# ST-Link_V3E.net
KiCad netlist of a schematic drawn in Altium Designer
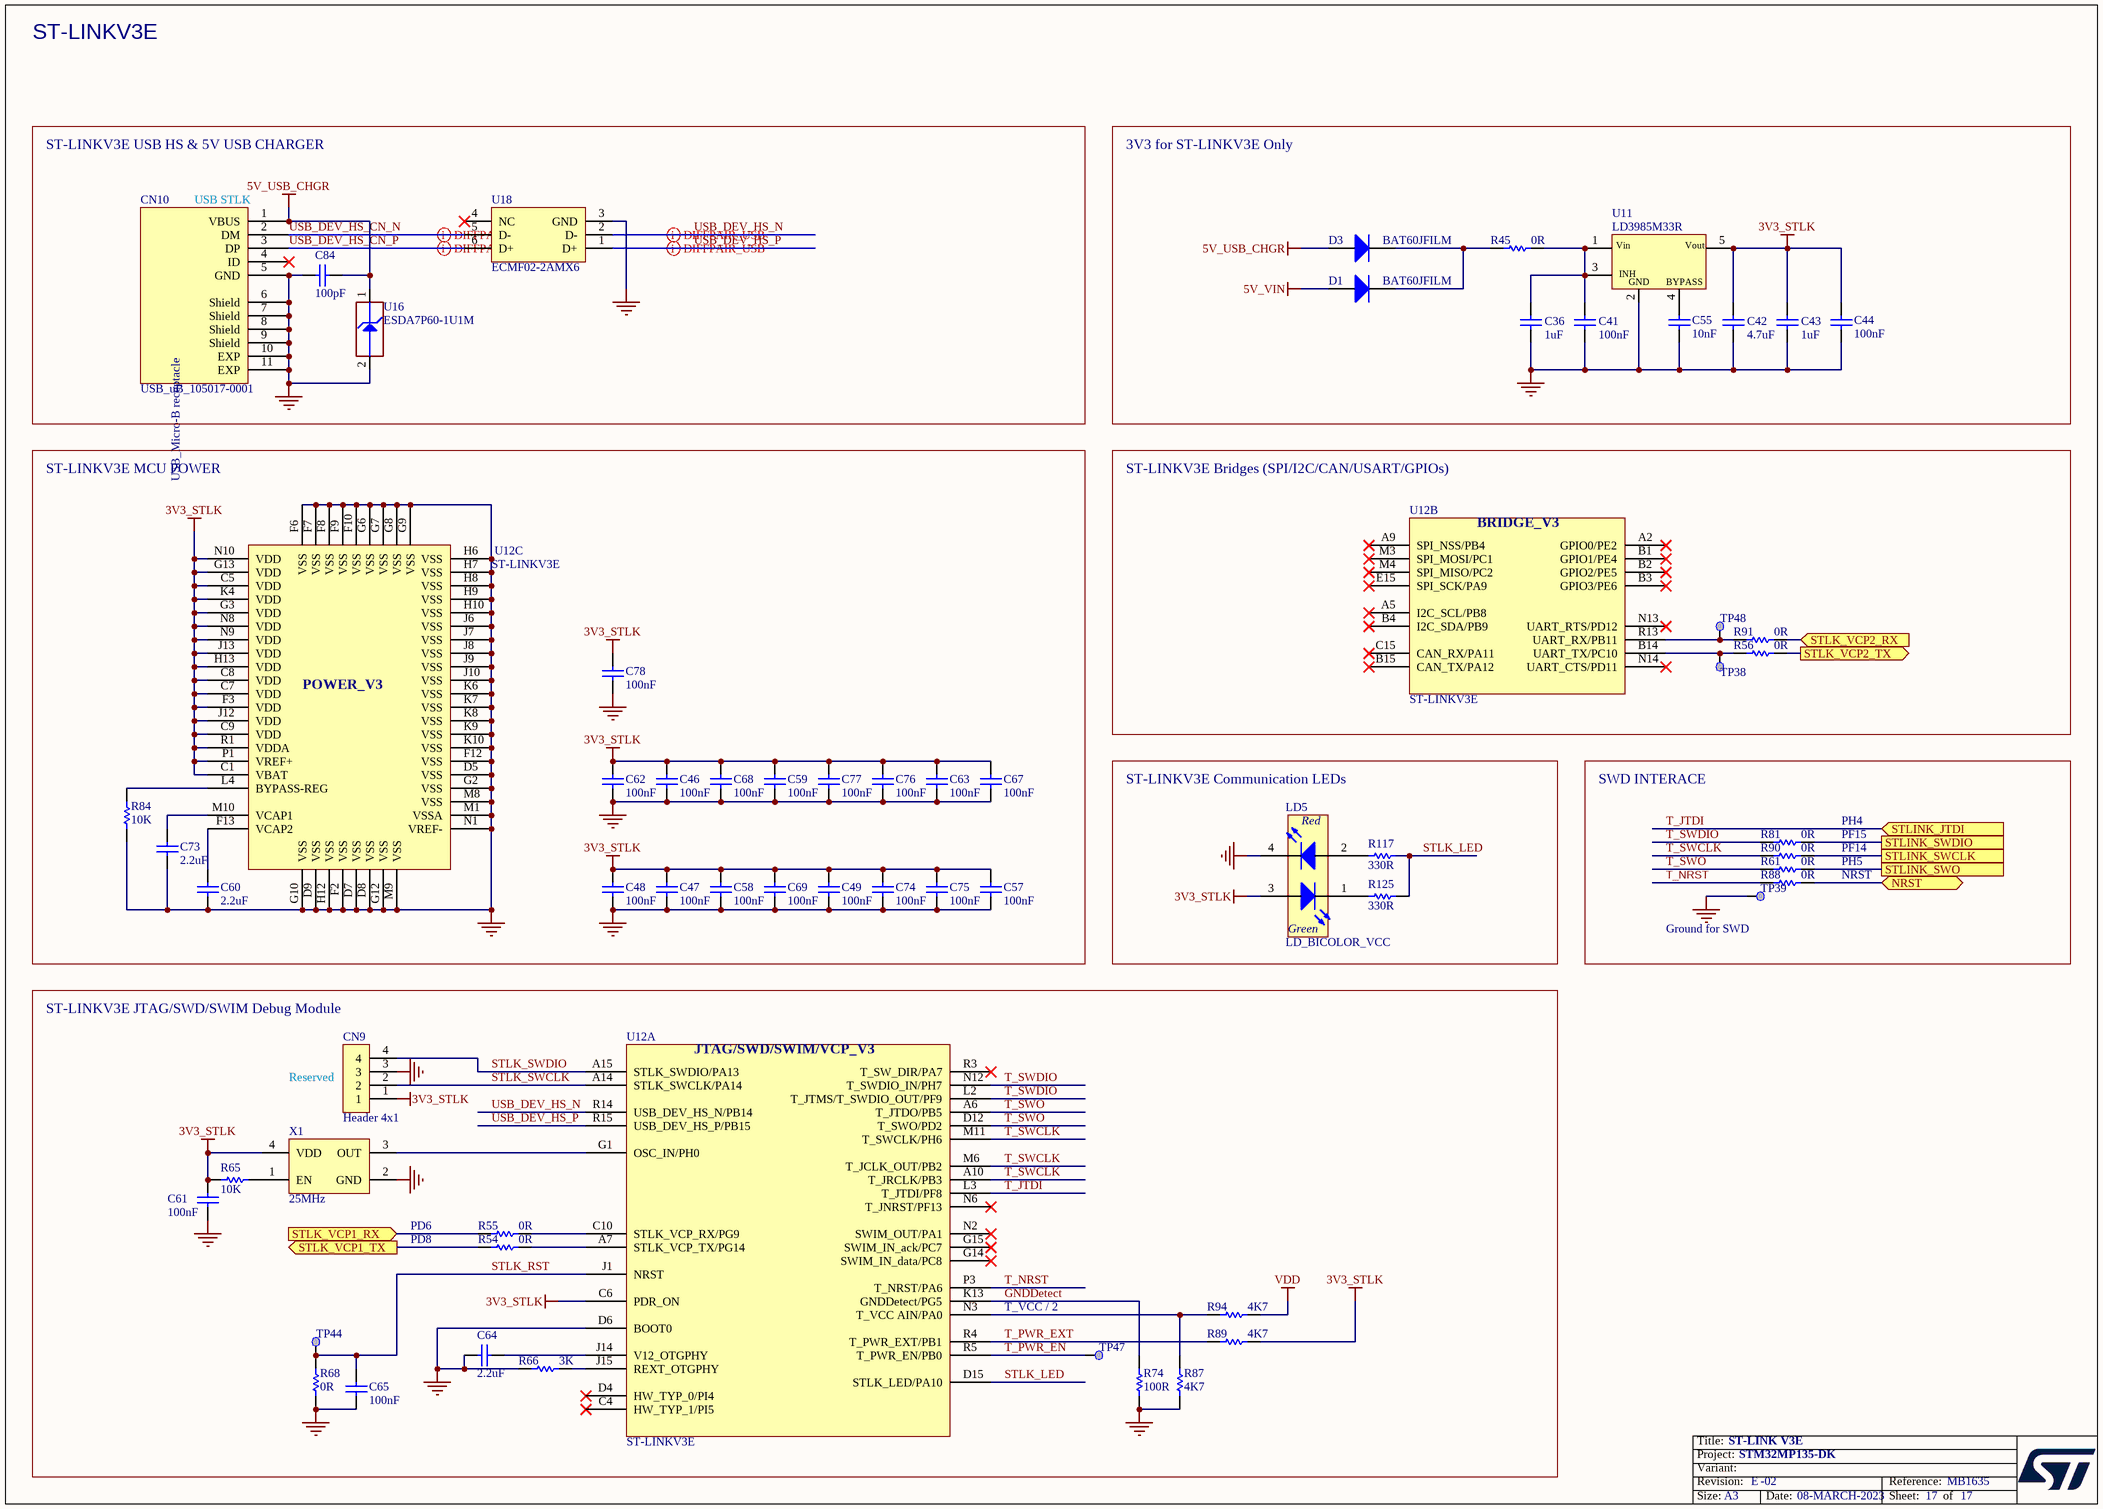
[diagram p0: ST-Link_V3E.SchDoc]

(export (version "E")
  (design (tool "Eeschema 10.0.6"))
  (components
    (comp (ref "C36")
      (value "1uF")
      (footprint "C0402")
      (description "Capacitor, MLCC, 1uF, 25V, X5R, +/-10%, 0402, T=0.5mm")
      (fields
        (field (name "INTERNAL_PART_NUMBER") "MCD-00095")
        (field (name "MANUFACTURER_PART_NUMBER") "GRM155R61E105KA12")
      )
      (libsource (lib "MCD_PARTS_database") (part "Capacitor"))
    )
    (comp (ref "C41")
      (value "100nF")
      (footprint "C0402")
      (description "Capacitor, MLCC, 100nF, 16V, X7R, +/-10%, 0402, T=0.5mm")
      (fields
        (field (name "INTERNAL_PART_NUMBER") "MCD-00006")
        (field (name "MANUFACTURER_PART_NUMBER") "CC0402KRX7R7BB104")
      )
      (libsource (lib "MCD_PARTS_database") (part "Capacitor"))
    )
    (comp (ref "C42")
      (value "4.7uF")
      (footprint "C0402")
      (description "Capacitor, MLCC, 4.7uF, 6V3, X5R, +/-20%, 0402, T=0.5mm")
      (fields
        (field (name "INTERNAL_PART_NUMBER") "MCD-01356")
        (field (name "MANUFACTURER_PART_NUMBER") "GRM155R60J475ME47")
      )
      (libsource (lib "MCD_PARTS_database") (part "Capacitor"))
    )
    (comp (ref "C43")
      (value "1uF")
      (footprint "C0402")
      (description "Capacitor, MLCC, 1uF, 25V, X5R, +/-10%, 0402, T=0.5mm")
      (fields
        (field (name "INTERNAL_PART_NUMBER") "MCD-00095")
        (field (name "MANUFACTURER_PART_NUMBER") "GRM155R61E105KA12")
      )
      (libsource (lib "MCD_PARTS_database") (part "Capacitor"))
    )
    (comp (ref "C44")
      (value "100nF")
      (footprint "C0402")
      (description "Capacitor, MLCC, 100nF, 16V, X7R, +/-10%, 0402, T=0.5mm")
      (fields
        (field (name "INTERNAL_PART_NUMBER") "MCD-00006")
        (field (name "MANUFACTURER_PART_NUMBER") "CC0402KRX7R7BB104")
      )
      (libsource (lib "MCD_PARTS_database") (part "Capacitor"))
    )
    (comp (ref "C46")
      (value "100nF")
      (footprint "C0402")
      (description "Capacitor, MLCC, 100nF, 16V, X7R, +/-10%, 0402, T=0.5mm")
      (fields
        (field (name "INTERNAL_PART_NUMBER") "MCD-00006")
        (field (name "MANUFACTURER_PART_NUMBER") "CC0402KRX7R7BB104")
      )
      (libsource (lib "MCD_PARTS_database") (part "Capacitor"))
    )
    (comp (ref "C47")
      (value "100nF")
      (footprint "C0402")
      (description "Capacitor, MLCC, 100nF, 16V, X7R, +/-10%, 0402, T=0.5mm")
      (fields
        (field (name "INTERNAL_PART_NUMBER") "MCD-00006")
        (field (name "MANUFACTURER_PART_NUMBER") "CC0402KRX7R7BB104")
      )
      (libsource (lib "MCD_PARTS_database") (part "Capacitor"))
    )
    (comp (ref "C48")
      (value "100nF")
      (footprint "C0402")
      (description "Capacitor, MLCC, 100nF, 16V, X7R, +/-10%, 0402, T=0.5mm")
      (fields
        (field (name "INTERNAL_PART_NUMBER") "MCD-00006")
        (field (name "MANUFACTURER_PART_NUMBER") "CC0402KRX7R7BB104")
      )
      (libsource (lib "MCD_PARTS_database") (part "Capacitor"))
    )
    (comp (ref "C49")
      (value "100nF")
      (footprint "C0402")
      (description "Capacitor, MLCC, 100nF, 16V, X7R, +/-10%, 0402, T=0.5mm")
      (fields
        (field (name "INTERNAL_PART_NUMBER") "MCD-00006")
        (field (name "MANUFACTURER_PART_NUMBER") "CC0402KRX7R7BB104")
      )
      (libsource (lib "MCD_PARTS_database") (part "Capacitor"))
    )
    (comp (ref "C55")
      (value "10nF")
      (footprint "C0402")
      (description "Capacitor, MLCC, 10nF, 50V, X7R, +/-10%, 0402, T=0.5mm")
      (fields
        (field (name "INTERNAL_PART_NUMBER") "MCD-02198")
        (field (name "MANUFACTURER_PART_NUMBER") "CC0402KRX7R9BB103")
      )
      (libsource (lib "MCD_PARTS_database") (part "Capacitor"))
    )
    (comp (ref "C57")
      (value "100nF")
      (footprint "C0402")
      (description "Capacitor, MLCC, 100nF, 16V, X7R, +/-10%, 0402, T=0.5mm")
      (fields
        (field (name "INTERNAL_PART_NUMBER") "MCD-00006")
        (field (name "MANUFACTURER_PART_NUMBER") "CC0402KRX7R7BB104")
      )
      (libsource (lib "MCD_PARTS_database") (part "Capacitor"))
    )
    (comp (ref "C58")
      (value "100nF")
      (footprint "C0402")
      (description "Capacitor, MLCC, 100nF, 16V, X7R, +/-10%, 0402, T=0.5mm")
      (fields
        (field (name "INTERNAL_PART_NUMBER") "MCD-00006")
        (field (name "MANUFACTURER_PART_NUMBER") "CC0402KRX7R7BB104")
      )
      (libsource (lib "MCD_PARTS_database") (part "Capacitor"))
    )
    (comp (ref "C59")
      (value "100nF")
      (footprint "C0402")
      (description "Capacitor, MLCC, 100nF, 16V, X7R, +/-10%, 0402, T=0.5mm")
      (fields
        (field (name "INTERNAL_PART_NUMBER") "MCD-00006")
        (field (name "MANUFACTURER_PART_NUMBER") "CC0402KRX7R7BB104")
      )
      (libsource (lib "MCD_PARTS_database") (part "Capacitor"))
    )
    (comp (ref "C60")
      (value "2.2uF")
      (footprint "C0201_H0P5")
      (description "Capacitor, MLCC, 2.2uF, 10V, X5R,+/-10%, 0201, T=0.5mm")
      (fields
        (field (name "INTERNAL_PART_NUMBER") "MCD-02235")
        (field (name "MANUFACTURER_PART_NUMBER") "GRM033R61A225KE47D")
      )
      (libsource (lib "MCD_PARTS_database") (part "Capacitor"))
    )
    (comp (ref "C61")
      (value "100nF")
      (footprint "C0402")
      (description "Capacitor, MLCC, 100nF, 16V, X7R, +/-10%, 0402, T=0.5mm")
      (fields
        (field (name "INTERNAL_PART_NUMBER") "MCD-00006")
        (field (name "MANUFACTURER_PART_NUMBER") "CC0402KRX7R7BB104")
      )
      (libsource (lib "MCD_PARTS_database") (part "Capacitor"))
    )
    (comp (ref "C62")
      (value "100nF")
      (footprint "C0402")
      (description "Capacitor, MLCC, 100nF, 16V, X7R, +/-10%, 0402, T=0.5mm")
      (fields
        (field (name "INTERNAL_PART_NUMBER") "MCD-00006")
        (field (name "MANUFACTURER_PART_NUMBER") "CC0402KRX7R7BB104")
      )
      (libsource (lib "MCD_PARTS_database") (part "Capacitor"))
    )
    (comp (ref "C63")
      (value "100nF")
      (footprint "C0402")
      (description "Capacitor, MLCC, 100nF, 16V, X7R, +/-10%, 0402, T=0.5mm")
      (fields
        (field (name "INTERNAL_PART_NUMBER") "MCD-00006")
        (field (name "MANUFACTURER_PART_NUMBER") "CC0402KRX7R7BB104")
      )
      (libsource (lib "MCD_PARTS_database") (part "Capacitor"))
    )
    (comp (ref "C64")
      (value "2.2uF")
      (footprint "C0201_H0P5")
      (description "Capacitor, MLCC, 2.2uF, 10V, X5R,+/-10%, 0201, T=0.5mm")
      (fields
        (field (name "INTERNAL_PART_NUMBER") "MCD-02235")
        (field (name "MANUFACTURER_PART_NUMBER") "GRM033R61A225KE47D")
      )
      (libsource (lib "MCD_PARTS_database") (part "Capacitor"))
    )
    (comp (ref "C65")
      (value "100nF")
      (footprint "C0402")
      (description "Capacitor, MLCC, 100nF, 16V, X7R, +/-10%, 0402, T=0.5mm")
      (fields (field (name "INTERNAL_PART_NUMBER") "MCD-00006") (field (name "MANUFACTURER") "YAGEO"))
      (libsource (lib "MCD_PARTS_database") (part "Capacitor"))
    )
    (comp (ref "C67")
      (value "100nF")
      (footprint "C0402")
      (description "Capacitor, MLCC, 100nF, 16V, X7R, +/-10%, 0402, T=0.5mm")
      (fields
        (field (name "INTERNAL_PART_NUMBER") "MCD-00006")
        (field (name "MANUFACTURER_PART_NUMBER") "CC0402KRX7R7BB104")
      )
      (libsource (lib "MCD_PARTS_database") (part "Capacitor"))
    )
    (comp (ref "C68")
      (value "100nF")
      (footprint "C0402")
      (description "Capacitor, MLCC, 100nF, 16V, X7R, +/-10%, 0402, T=0.5mm")
      (fields
        (field (name "INTERNAL_PART_NUMBER") "MCD-00006")
        (field (name "MANUFACTURER_PART_NUMBER") "CC0402KRX7R7BB104")
      )
      (libsource (lib "MCD_PARTS_database") (part "Capacitor"))
    )
    (comp (ref "C69")
      (value "100nF")
      (footprint "C0402")
      (description "Capacitor, MLCC, 100nF, 16V, X7R, +/-10%, 0402, T=0.5mm")
      (fields
        (field (name "INTERNAL_PART_NUMBER") "MCD-00006")
        (field (name "MANUFACTURER_PART_NUMBER") "CC0402KRX7R7BB104")
      )
      (libsource (lib "MCD_PARTS_database") (part "Capacitor"))
    )
    (comp (ref "C73")
      (value "2.2uF")
      (footprint "C0201_H0P5")
      (description "Capacitor, MLCC, 2.2uF, 10V, X5R,+/-10%, 0201, T=0.5mm")
      (fields
        (field (name "INTERNAL_PART_NUMBER") "MCD-02235")
        (field (name "MANUFACTURER_PART_NUMBER") "GRM033R61A225KE47D")
      )
      (libsource (lib "MCD_PARTS_database") (part "Capacitor"))
    )
    (comp (ref "C74")
      (value "100nF")
      (footprint "C0402")
      (description "Capacitor, MLCC, 100nF, 16V, X7R, +/-10%, 0402, T=0.5mm")
      (fields
        (field (name "INTERNAL_PART_NUMBER") "MCD-00006")
        (field (name "MANUFACTURER_PART_NUMBER") "CC0402KRX7R7BB104")
      )
      (libsource (lib "MCD_PARTS_database") (part "Capacitor"))
    )
    (comp (ref "C75")
      (value "100nF")
      (footprint "C0402")
      (description "Capacitor, MLCC, 100nF, 16V, X7R, +/-10%, 0402, T=0.5mm")
      (fields
        (field (name "INTERNAL_PART_NUMBER") "MCD-00006")
        (field (name "MANUFACTURER_PART_NUMBER") "CC0402KRX7R7BB104")
      )
      (libsource (lib "MCD_PARTS_database") (part "Capacitor"))
    )
    (comp (ref "C76")
      (value "100nF")
      (footprint "C0402")
      (description "Capacitor, MLCC, 100nF, 16V, X7R, +/-10%, 0402, T=0.5mm")
      (fields
        (field (name "INTERNAL_PART_NUMBER") "MCD-00006")
        (field (name "MANUFACTURER_PART_NUMBER") "CC0402KRX7R7BB104")
      )
      (libsource (lib "MCD_PARTS_database") (part "Capacitor"))
    )
    (comp (ref "C77")
      (value "100nF")
      (footprint "C0402")
      (description "Capacitor, MLCC, 100nF, 16V, X7R, +/-10%, 0402, T=0.5mm")
      (fields
        (field (name "INTERNAL_PART_NUMBER") "MCD-00006")
        (field (name "MANUFACTURER_PART_NUMBER") "CC0402KRX7R7BB104")
      )
      (libsource (lib "MCD_PARTS_database") (part "Capacitor"))
    )
    (comp (ref "C78")
      (value "100nF")
      (footprint "C0402")
      (description "Capacitor, MLCC, 100nF, 16V, X7R, +/-10%, 0402, T=0.5mm")
      (fields
        (field (name "INTERNAL_PART_NUMBER") "MCD-00006")
        (field (name "MANUFACTURER_PART_NUMBER") "CC0402KRX7R7BB104")
      )
      (libsource (lib "MCD_PARTS_database") (part "Capacitor"))
    )
    (comp (ref "C84")
      (value "100pF")
      (footprint "C0402")
      (description "Capacitor, MLCC, 100pF, 50V, NPO, +/-5%, 0402, T=0.5mm")
      (fields
        (field (name "INTERNAL_PART_NUMBER") "MCD-00205")
        (field (name "MANUFACTURER_PART_NUMBER") "CC0402JRNPO9BN101")
      )
      (libsource (lib "MCD_PARTS_database") (part "Capacitor"))
    )
    (comp (ref "CN9")
      (value "Header 4x1")
      (footprint "CON_SAMTEC_TSW-104-07-G-S")
      (description "Header, 4x1, 2.54mm, VR, TH, T=5.84mm/2.54mm")
      (fields
        (field (name "INTERNAL_PART_NUMBER") "MCD-00029")
        (field (name "MANUFACTURER_PART_NUMBER") "TSW-104-07-G-S")
      )
      (libsource (lib "MCD_PARTS_database") (part "Header 4x1"))
    )
    (comp (ref "CN10")
      (value "USB_uB_105017-0001")
      (footprint "CON_USBMICROB_MOLEX_105017-0001_H2P90")
      (description "MicroUSB_TypeB, 5pins, 0.65mm, RA, SMD, T=2.9mm")
      (fields
        (field (name "INTERNAL_PART_NUMBER") "MCD-00028")
        (field (name "MANUFACTURER_PART_NUMBER") "1050170001")
      )
      (libsource (lib "MCD_PARTS_database") (part "USB_uB_105017.0001"))
    )
    (comp (ref "D1")
      (value "BAT60JFILM")
      (footprint "DIO_SOD323")
      (fields
        (field (name "INTERNAL_PART_NUMBER") "MCD-00034")
        (field (name "MANUFACTURER") "STMICROELECTRONICS")
        (field (name "BMS_PART_NUMBER") "9151097")
      )
      (libsource (lib "MCD_PARTS_database") (part "BAT60JFILM"))
    )
    (comp (ref "D3")
      (value "BAT60JFILM")
      (footprint "DIO_SOD323")
      (fields
        (field (name "INTERNAL_PART_NUMBER") "MCD-00034")
        (field (name "MANUFACTURER") "STMICROELECTRONICS")
        (field (name "BMS_PART_NUMBER") "9151097")
      )
      (libsource (lib "MCD_PARTS_database") (part "BAT60JFILM"))
    )
    (comp (ref "LD5")
      (value "LD_BICOLOR_VCC")
      (footprint "LED_BI-GR_CMD67-22")
      (description "LED Bicolor, Green, Red, 4-PLCC")
      (fields
        (field (name "INTERNAL_PART_NUMBER") "MCD-02629")
        (field (name "MANUFACTURER_PART_NUMBER") "CMD6722VRVGCTR8")
      )
      (libsource (lib "MCD_PARTS_database") (part "LD_BICOLOR_VCC"))
    )
    (comp (ref "R45")
      (value "0R")
      (footprint "R0402")
      (description "Resistor, 0R, 0402, +/-5%, 1/16W")
      (fields (field (name "INTERNAL_PART_NUMBER") "MCD-00052") (field (name "MANUFACTURER") "YAGEO"))
      (libsource (lib "MCD_PARTS_database") (part "Resistor"))
    )
    (comp (ref "R54")
      (value "0R")
      (footprint "R0402")
      (description "Resistor, 0R, 0402, +/-5%, 1/16W")
      (fields
        (field (name "INTERNAL_PART_NUMBER") "MCD-00052")
        (field (name "MANUFACTURER_PART_NUMBER") "RC0402JR-070RL")
      )
      (libsource (lib "MCD_PARTS_database") (part "Resistor"))
    )
    (comp (ref "R55")
      (value "0R")
      (footprint "R0402")
      (description "Resistor, 0R, 0402, +/-5%, 1/16W")
      (fields
        (field (name "INTERNAL_PART_NUMBER") "MCD-00052")
        (field (name "MANUFACTURER_PART_NUMBER") "RC0402JR-070RL")
      )
      (libsource (lib "MCD_PARTS_database") (part "Resistor"))
    )
    (comp (ref "R56")
      (value "0R")
      (footprint "R0402")
      (description "Resistor, 0R, 0402, +/-5%, 1/16W")
      (fields
        (field (name "INTERNAL_PART_NUMBER") "MCD-00052")
        (field (name "MANUFACTURER_PART_NUMBER") "RC0402JR-070RL")
      )
      (libsource (lib "MCD_PARTS_database") (part "Resistor"))
    )
    (comp (ref "R61")
      (value "0R")
      (footprint "R0402")
      (description "Resistor, 0R, 0402, +/-5%, 1/16W")
      (fields (field (name "INTERNAL_PART_NUMBER") "MCD-00052") (field (name "MANUFACTURER") "YAGEO"))
      (libsource (lib "MCD_PARTS_database") (part "Resistor"))
    )
    (comp (ref "R65")
      (value "10K")
      (footprint "R0402")
      (description "Resistor, 10K, 0402, +/-1%, 1/16W")
      (fields
        (field (name "INTERNAL_PART_NUMBER") "MCD-00053")
        (field (name "MANUFACTURER_PART_NUMBER") "RC0402FR-0710KL")
      )
      (libsource (lib "MCD_PARTS_database") (part "Resistor"))
    )
    (comp (ref "R66")
      (value "3K")
      (footprint "R0402")
      (description "Resistor, 3K, 0402, +/-1%, 1/16W")
      (fields
        (field (name "INTERNAL_PART_NUMBER") "MCD-00185")
        (field (name "MANUFACTURER_PART_NUMBER") "RC0402FR-073KL")
      )
      (libsource (lib "MCD_PARTS_database") (part "Resistor"))
    )
    (comp (ref "R68")
      (value "0R")
      (footprint "R0402")
      (description "Resistor, 0R, 0402, +/-5%, 1/16W")
      (fields
        (field (name "INTERNAL_PART_NUMBER") "MCD-00052")
        (field (name "MANUFACTURER_PART_NUMBER") "RC0402JR-070RL")
      )
      (libsource (lib "MCD_PARTS_database") (part "Resistor"))
    )
    (comp (ref "R74")
      (value "100R")
      (footprint "R0402")
      (description "Resistor, 100R, 0402, +/- 1%, 1/16W")
      (fields
        (field (name "INTERNAL_PART_NUMBER") "MCD-00067")
        (field (name "MANUFACTURER_PART_NUMBER") "RC0402FR-07100RL")
      )
      (libsource (lib "MCD_PARTS_database") (part "Resistor"))
    )
    (comp (ref "R81")
      (value "0R")
      (footprint "R0402")
      (description "Resistor, 0R, 0402, +/-5%, 1/16W")
      (fields (field (name "INTERNAL_PART_NUMBER") "MCD-00052") (field (name "MANUFACTURER") "YAGEO"))
      (libsource (lib "MCD_PARTS_database") (part "Resistor"))
    )
    (comp (ref "R84")
      (value "10K")
      (footprint "R0402")
      (description "Resistor, 10K, 0402, +/-1%, 1/16W")
      (fields
        (field (name "INTERNAL_PART_NUMBER") "MCD-00053")
        (field (name "MANUFACTURER_PART_NUMBER") "RC0402FR-0710KL")
      )
      (libsource (lib "MCD_PARTS_database") (part "Resistor"))
    )
    (comp (ref "R87")
      (value "4K7")
      (footprint "R0402")
      (description "Resistor, 4K7, 0402, +/-1%, 1/16W")
      (fields
        (field (name "INTERNAL_PART_NUMBER") "MCD-00065")
        (field (name "MANUFACTURER_PART_NUMBER") "RC0402FR-074K7L")
      )
      (libsource (lib "MCD_PARTS_database") (part "Resistor"))
    )
    (comp (ref "R88")
      (value "0R")
      (footprint "R0402")
      (description "Resistor, 0R, 0402, +/-5%, 1/16W")
      (fields (field (name "INTERNAL_PART_NUMBER") "MCD-00052") (field (name "MANUFACTURER") "YAGEO"))
      (libsource (lib "MCD_PARTS_database") (part "Resistor"))
    )
    (comp (ref "R89")
      (value "4K7")
      (footprint "R0402")
      (description "Resistor, 4K7, 0402, +/-1%, 1/16W")
      (fields
        (field (name "INTERNAL_PART_NUMBER") "MCD-00065")
        (field (name "MANUFACTURER_PART_NUMBER") "RC0402FR-074K7L")
      )
      (libsource (lib "MCD_PARTS_database") (part "Resistor"))
    )
    (comp (ref "R90")
      (value "0R")
      (footprint "R0402")
      (description "Resistor, 0R, 0402, +/-5%, 1/16W")
      (fields (field (name "INTERNAL_PART_NUMBER") "MCD-00052") (field (name "MANUFACTURER") "YAGEO"))
      (libsource (lib "MCD_PARTS_database") (part "Resistor"))
    )
    (comp (ref "R91")
      (value "0R")
      (footprint "R0402")
      (description "Resistor, 0R, 0402, +/-5%, 1/16W")
      (fields
        (field (name "INTERNAL_PART_NUMBER") "MCD-00052")
        (field (name "MANUFACTURER_PART_NUMBER") "RC0402JR-070RL")
      )
      (libsource (lib "MCD_PARTS_database") (part "Resistor"))
    )
    (comp (ref "R94")
      (value "4K7")
      (footprint "R0402")
      (description "Resistor, 4K7, 0402, +/-1%, 1/16W")
      (fields
        (field (name "INTERNAL_PART_NUMBER") "MCD-00065")
        (field (name "MANUFACTURER_PART_NUMBER") "RC0402FR-074K7L")
      )
      (libsource (lib "MCD_PARTS_database") (part "Resistor"))
    )
    (comp (ref "R117")
      (value "330R")
      (footprint "R0402")
      (description "Resistor, 330R, 0402, +/-1%, 1/16W")
      (fields
        (field (name "INTERNAL_PART_NUMBER") "MCD-00062")
        (field (name "MANUFACTURER_PART_NUMBER") "RC0402FR-07330RL")
      )
      (libsource (lib "MCD_PARTS_database") (part "Resistor"))
    )
    (comp (ref "R125")
      (value "330R")
      (footprint "R0402")
      (description "Resistor, 330R, 0402, +/-1%, 1/16W")
      (fields
        (field (name "INTERNAL_PART_NUMBER") "MCD-00062")
        (field (name "MANUFACTURER_PART_NUMBER") "RC0402FR-07330RL")
      )
      (libsource (lib "MCD_PARTS_database") (part "Resistor"))
    )
    (comp (ref "TP38")
      (value "Test Point")
      (footprint "TP_SMD_1MM")
      (description "Test Point 1mm")
      (fields (field (name "INTERNAL_PART_NUMBER") "MCD-00074"))
      (libsource (lib "") (part "Test Point_2"))
    )
    (comp (ref "TP39")
      (value "Test Point")
      (footprint "TP_SMD_1MM")
      (description "Test Point 1mm")
      (fields (field (name "INTERNAL_PART_NUMBER") "MCD-00074"))
      (libsource (lib "") (part "Test Point_1"))
    )
    (comp (ref "TP44")
      (value "Test Point")
      (footprint "TP_SMD_1MM")
      (description "Test Point 1mm")
      (fields (field (name "INTERNAL_PART_NUMBER") "MCD-00074"))
      (libsource (lib "MCD_PARTS_database") (part "Test Point"))
    )
    (comp (ref "TP47")
      (value "Test Point")
      (footprint "TP_SMD_1MM")
      (description "Test Point 1mm")
      (fields (field (name "INTERNAL_PART_NUMBER") "MCD-00074"))
      (libsource (lib "") (part "Test Point_1"))
    )
    (comp (ref "TP48")
      (value "Test Point")
      (footprint "TP_SMD_1MM")
      (description "Test Point 1mm")
      (fields (field (name "INTERNAL_PART_NUMBER") "MCD-00074"))
      (libsource (lib "MCD_PARTS_database") (part "Test Point"))
    )
    (comp (ref "U11")
      (value "LD3985M33R")
      (footprint "REG_SOT23-5L")
      (description "Ultra low drop-low noise BiCMOS voltage, regulators low ESR capacitors compatible")
      (fields (field (name "INTERNAL_PART_NUMBER") "MCD-00086") (field (name "BMS_PART_NUMBER") "9176161"))
      (libsource (lib "MCD_PARTS_database") (part "LD3985M33R"))
    )
    (comp (ref "U12")
      (value "ST-LINKV3E")
      (footprint "ICC_UFBGA201_176+25_10X10_P065")
      (description "MCU, Arm Cortex-M7 32-bit MCU, 512KB Flash, 276KB RAM, With Crypto")
      (fields
        (field (name "INTERNAL_PART_NUMBER") "MCD-01523")
        (field (name "MANUFACTURER_PART_NUMBER") "STM32F723IEK6")
      )
      (libsource (lib "MCD_PARTS_database") (part "ST-LINKV3S"))
    )
    (comp (ref "U16")
      (value "ESDA7P60-1U1M")
      (footprint "ESD_QFN2_1P6X1_P125")
      (description "High power transient voltage suppressor, 7V breakdown")
      (fields
        (field (name "INTERNAL_PART_NUMBER") "MCD-00251")
        (field (name "MANUFACTURER") "STMICROELECTRONICS")
      )
      (libsource (lib "MCD_PARTS_database") (part "ESD-TRANSIL"))
    )
    (comp (ref "U18")
      (value "ECMF02-2AMX6")
      (footprint "ESD_QFN-6L_1P7X1P5_P050")
      (description "Common mode filter with ESD protection for USB 2.0 interface")
      (fields
        (field (name "INTERNAL_PART_NUMBER") "MCD-00649")
        (field (name "MANUFACTURER") "STMICROELECTRONICS")
      )
      (libsource (lib "MCD_PARTS_database") (part "ECMF02-2AMX6"))
    )
    (comp (ref "X1")
      (value "25MHz")
      (footprint "OSC_NDK_NZ2520SB_4P")
      (description "Oscillator, SPXO, 25Mhz, +/-50ppm, 3V3, square wave, 2.5x2mm")
      (fields
        (field (name "INTERNAL_PART_NUMBER") "MCD-00597")
        (field (name "MANUFACTURER_PART_NUMBER") "NZ2520SH-25MHZ-END4869C")
      )
      (libsource (lib "MCD_PARTS_database") (part "OSCILLATOR_4_PINS"))
    )
  )
  (nets
    (net (code "1") (name "/GNDDetect") (class "Default")
      (node (ref "R74") (pin "2") (pinfunction "2_2") (pintype "passive"))
      (node (ref "U12") (pin "K13") (pinfunction "GNDDetect/PG5_K13") (pintype "passive"))
    )
    (net (code "2") (name "/NRST") (class "Default")
      (node (ref "R88") (pin "2") (pinfunction "2_2") (pintype "passive"))
    )
    (net (code "3") (name "/STLINK_SWCLK") (class "Default")
      (node (ref "R90") (pin "2") (pinfunction "2_2") (pintype "passive"))
    )
    (net (code "4") (name "/STLINK_SWDIO") (class "Default")
      (node (ref "R81") (pin "2") (pinfunction "2_2") (pintype "passive"))
    )
    (net (code "5") (name "/STLINK_SWO") (class "Default")
      (node (ref "R61") (pin "2") (pinfunction "2_2") (pintype "passive"))
    )
    (net (code "6") (name "/STLK_LED") (class "Default")
      (node (ref "R117") (pin "2") (pinfunction "2_2") (pintype "passive"))
      (node (ref "R125") (pin "2") (pinfunction "2_2") (pintype "passive"))
      (node (ref "U12") (pin "D15") (pinfunction "STLK_LED/PA10_D15") (pintype "passive"))
    )
    (net (code "7") (name "/STLK_RST") (class "Default")
      (node (ref "C65") (pin "2") (pinfunction "2_2") (pintype "passive"))
      (node (ref "R68") (pin "1") (pinfunction "1_1") (pintype "passive"))
      (node (ref "TP44") (pin "1") (pinfunction "1_1") (pintype "passive"))
      (node (ref "U12") (pin "J1") (pinfunction "NRST_J1") (pintype "passive"))
    )
    (net (code "8") (name "/STLK_SWCLK") (class "Default")
      (node (ref "CN9") (pin "2") (pinfunction "2_2") (pintype "passive"))
      (node (ref "U12") (pin "A14") (pinfunction "STLK_SWCLK/PA14_A14") (pintype "passive"))
    )
    (net (code "9") (name "/STLK_SWDIO") (class "Default")
      (node (ref "CN9") (pin "4") (pinfunction "4_4") (pintype "passive"))
      (node (ref "U12") (pin "A15") (pinfunction "STLK_SWDIO/PA13_A15") (pintype "passive"))
    )
    (net (code "10") (name "/STLK_VCP1_RX") (class "Default")
      (node (ref "R55") (pin "2") (pinfunction "2_2") (pintype "passive"))
    )
    (net (code "11") (name "/STLK_VCP1_TX") (class "Default")
      (node (ref "R54") (pin "2") (pinfunction "2_2") (pintype "passive"))
    )
    (net (code "12") (name "/STLK_VCP2_RX") (class "Default")
      (node (ref "R91") (pin "1") (pinfunction "1_1") (pintype "passive"))
    )
    (net (code "13") (name "/STLK_VCP2_TX") (class "Default")
      (node (ref "R56") (pin "1") (pinfunction "1_1") (pintype "passive"))
    )
    (net (code "14") (name "/T_JTDI") (class "Default")
      (node (ref "U12") (pin "L3") (pinfunction "T_JTDI/PF8_L3") (pintype "passive"))
    )
    (net (code "15") (name "/T_NRST") (class "Default")
      (node (ref "R88") (pin "1") (pinfunction "1_1") (pintype "passive"))
      (node (ref "U12") (pin "P3") (pinfunction "T_NRST/PA6_P3") (pintype "passive"))
    )
    (net (code "16") (name "/T_PWR_EN") (class "Default")
      (node (ref "TP47") (pin "1") (pinfunction "1_1") (pintype "passive"))
      (node (ref "U12") (pin "R5") (pinfunction "T_PWR_EN/PB0_R5") (pintype "passive"))
    )
    (net (code "17") (name "/T_PWR_EXT") (class "Default")
      (node (ref "R89") (pin "2") (pinfunction "2_2") (pintype "passive"))
      (node (ref "U12") (pin "R4") (pinfunction "T_PWR_EXT/PB1_R4") (pintype "passive"))
    )
    (net (code "18") (name "/T_SWCLK") (class "Default")
      (node (ref "R90") (pin "1") (pinfunction "1_1") (pintype "passive"))
      (node (ref "U12") (pin "A10") (pinfunction "T_JRCLK/PB3_A10") (pintype "passive"))
      (node (ref "U12") (pin "M11") (pinfunction "T_SWCLK/PH6_M11") (pintype "passive"))
      (node (ref "U12") (pin "M6") (pinfunction "T_JCLK_OUT/PB2_M6") (pintype "passive"))
    )
    (net (code "19") (name "/T_SWDIO") (class "Default")
      (node (ref "R81") (pin "1") (pinfunction "1_1") (pintype "passive"))
      (node (ref "U12") (pin "L2") (pinfunction "T_JTMS/T_SWDIO_OUT/PF9_L2") (pintype "passive"))
      (node (ref "U12") (pin "N12") (pinfunction "T_SWDIO_IN/PH7_N12") (pintype "passive"))
    )
    (net (code "20") (name "/T_SWO") (class "Default")
      (node (ref "R61") (pin "1") (pinfunction "1_1") (pintype "passive"))
      (node (ref "U12") (pin "A6") (pinfunction "T_JTDO/PB5_A6") (pintype "passive"))
      (node (ref "U12") (pin "D12") (pinfunction "T_SWO/PD2_D12") (pintype "passive"))
    )
    (net (code "21") (name "/USB_DEV_HS_CN_N") (class "Default")
      (node (ref "CN10") (pin "2") (pinfunction "DM_2") (pintype "passive"))
      (node (ref "U18") (pin "5") (pinfunction "D-_5") (pintype "passive"))
    )
    (net (code "22") (name "/USB_DEV_HS_CN_P") (class "Default")
      (node (ref "CN10") (pin "3") (pinfunction "DP_3") (pintype "passive"))
      (node (ref "U18") (pin "6") (pinfunction "D+_6") (pintype "passive"))
    )
    (net (code "23") (name "/USB_DEV_HS_N") (class "Default")
      (node (ref "U12") (pin "R14") (pinfunction "USB_DEV_HS_N/PB14_R14") (pintype "passive"))
      (node (ref "U18") (pin "2") (pinfunction "D-_2") (pintype "passive"))
    )
    (net (code "24") (name "/USB_DEV_HS_P") (class "Default")
      (node (ref "U12") (pin "R15") (pinfunction "USB_DEV_HS_P/PB15_R15") (pintype "passive"))
      (node (ref "U18") (pin "1") (pinfunction "D+_1") (pintype "passive"))
    )
    (net (code "25") (name "3V3_STLK") (class "Default")
      (node (ref "C42") (pin "2") (pinfunction "2_2") (pintype "passive"))
      (node (ref "C43") (pin "2") (pinfunction "2_2") (pintype "passive"))
      (node (ref "C44") (pin "2") (pinfunction "2_2") (pintype "passive"))
      (node (ref "C46") (pin "2") (pinfunction "2_2") (pintype "passive"))
      (node (ref "C47") (pin "2") (pinfunction "2_2") (pintype "passive"))
      (node (ref "C48") (pin "2") (pinfunction "2_2") (pintype "passive"))
      (node (ref "C49") (pin "2") (pinfunction "2_2") (pintype "passive"))
      (node (ref "C57") (pin "2") (pinfunction "2_2") (pintype "passive"))
      (node (ref "C58") (pin "2") (pinfunction "2_2") (pintype "passive"))
      (node (ref "C59") (pin "2") (pinfunction "2_2") (pintype "passive"))
      (node (ref "C61") (pin "2") (pinfunction "2_2") (pintype "passive"))
      (node (ref "C62") (pin "2") (pinfunction "2_2") (pintype "passive"))
      (node (ref "C63") (pin "2") (pinfunction "2_2") (pintype "passive"))
      (node (ref "C67") (pin "2") (pinfunction "2_2") (pintype "passive"))
      (node (ref "C68") (pin "2") (pinfunction "2_2") (pintype "passive"))
      (node (ref "C69") (pin "2") (pinfunction "2_2") (pintype "passive"))
      (node (ref "C74") (pin "2") (pinfunction "2_2") (pintype "passive"))
      (node (ref "C75") (pin "2") (pinfunction "2_2") (pintype "passive"))
      (node (ref "C76") (pin "2") (pinfunction "2_2") (pintype "passive"))
      (node (ref "C77") (pin "2") (pinfunction "2_2") (pintype "passive"))
      (node (ref "C78") (pin "2") (pinfunction "2_2") (pintype "passive"))
      (node (ref "CN9") (pin "1") (pinfunction "1_1") (pintype "passive"))
      (node (ref "LD5") (pin "3") (pinfunction "YellowGreen_anode_3") (pintype "passive"))
      (node (ref "R65") (pin "1") (pinfunction "1_1") (pintype "passive"))
      (node (ref "R89") (pin "1") (pinfunction "1_1") (pintype "passive"))
      (node (ref "U11") (pin "5") (pinfunction "Vout_5") (pintype "passive"))
      (node (ref "U12") (pin "C1") (pinfunction "VBAT_C1") (pintype "passive"))
      (node (ref "U12") (pin "C5") (pinfunction "VDD_C5") (pintype "passive"))
      (node (ref "U12") (pin "C6") (pinfunction "PDR_ON_C6") (pintype "passive"))
      (node (ref "U12") (pin "C7") (pinfunction "VDD_C7") (pintype "passive"))
      (node (ref "U12") (pin "C8") (pinfunction "VDD_C8") (pintype "passive"))
      (node (ref "U12") (pin "C9") (pinfunction "VDD_C9") (pintype "passive"))
      (node (ref "U12") (pin "F3") (pinfunction "VDD_F3") (pintype "passive"))
      (node (ref "U12") (pin "G13") (pinfunction "VDD_G13") (pintype "passive"))
      (node (ref "U12") (pin "G3") (pinfunction "VDD_G3") (pintype "passive"))
      (node (ref "U12") (pin "H13") (pinfunction "VDD_H13") (pintype "passive"))
      (node (ref "U12") (pin "J12") (pinfunction "VDD_J12") (pintype "passive"))
      (node (ref "U12") (pin "J13") (pinfunction "VDD_J13") (pintype "passive"))
      (node (ref "U12") (pin "K4") (pinfunction "VDD_K4") (pintype "passive"))
      (node (ref "U12") (pin "N10") (pinfunction "VDD_N10") (pintype "passive"))
      (node (ref "U12") (pin "N8") (pinfunction "VDD_N8") (pintype "passive"))
      (node (ref "U12") (pin "N9") (pinfunction "VDD_N9") (pintype "passive"))
      (node (ref "U12") (pin "P1") (pinfunction "VREF+_P1") (pintype "passive"))
      (node (ref "U12") (pin "R1") (pinfunction "VDDA_R1") (pintype "passive"))
      (node (ref "X1") (pin "4") (pinfunction "VDD_4") (pintype "passive"))
    )
    (net (code "26") (name "5V_USB_CHGR") (class "Default")
      (node (ref "C84") (pin "2") (pinfunction "2_2") (pintype "passive"))
      (node (ref "CN10") (pin "1") (pinfunction "VBUS_1") (pintype "passive"))
      (node (ref "D3") (pin "1") (pinfunction "A_1") (pintype "passive"))
      (node (ref "U16") (pin "1") (pinfunction "IO1_1") (pintype "passive"))
    )
    (net (code "27") (name "5V_VIN") (class "Default")
      (node (ref "D1") (pin "1") (pinfunction "A_1") (pintype "passive"))
    )
    (net (code "28") (name "GND") (class "Default")
      (node (ref "C36") (pin "2") (pinfunction "2_2") (pintype "passive"))
      (node (ref "C41") (pin "1") (pinfunction "1_1") (pintype "passive"))
      (node (ref "C42") (pin "1") (pinfunction "1_1") (pintype "passive"))
      (node (ref "C43") (pin "1") (pinfunction "1_1") (pintype "passive"))
      (node (ref "C44") (pin "1") (pinfunction "1_1") (pintype "passive"))
      (node (ref "C46") (pin "1") (pinfunction "1_1") (pintype "passive"))
      (node (ref "C47") (pin "1") (pinfunction "1_1") (pintype "passive"))
      (node (ref "C48") (pin "1") (pinfunction "1_1") (pintype "passive"))
      (node (ref "C49") (pin "1") (pinfunction "1_1") (pintype "passive"))
      (node (ref "C55") (pin "1") (pinfunction "1_1") (pintype "passive"))
      (node (ref "C57") (pin "1") (pinfunction "1_1") (pintype "passive"))
      (node (ref "C58") (pin "1") (pinfunction "1_1") (pintype "passive"))
      (node (ref "C59") (pin "1") (pinfunction "1_1") (pintype "passive"))
      (node (ref "C60") (pin "1") (pinfunction "1_1") (pintype "passive"))
      (node (ref "C61") (pin "1") (pinfunction "1_1") (pintype "passive"))
      (node (ref "C62") (pin "1") (pinfunction "1_1") (pintype "passive"))
      (node (ref "C63") (pin "1") (pinfunction "1_1") (pintype "passive"))
      (node (ref "C64") (pin "1") (pinfunction "1_1") (pintype "passive"))
      (node (ref "C65") (pin "1") (pinfunction "1_1") (pintype "passive"))
      (node (ref "C67") (pin "1") (pinfunction "1_1") (pintype "passive"))
      (node (ref "C68") (pin "1") (pinfunction "1_1") (pintype "passive"))
      (node (ref "C69") (pin "1") (pinfunction "1_1") (pintype "passive"))
      (node (ref "C73") (pin "1") (pinfunction "1_1") (pintype "passive"))
      (node (ref "C74") (pin "1") (pinfunction "1_1") (pintype "passive"))
      (node (ref "C75") (pin "1") (pinfunction "1_1") (pintype "passive"))
      (node (ref "C76") (pin "1") (pinfunction "1_1") (pintype "passive"))
      (node (ref "C77") (pin "1") (pinfunction "1_1") (pintype "passive"))
      (node (ref "C78") (pin "1") (pinfunction "1_1") (pintype "passive"))
      (node (ref "C84") (pin "1") (pinfunction "1_1") (pintype "passive"))
      (node (ref "CN10") (pin "10") (pinfunction "EXP_10") (pintype "passive"))
      (node (ref "CN10") (pin "11") (pinfunction "EXP_11") (pintype "passive"))
      (node (ref "CN10") (pin "5") (pinfunction "GND_5") (pintype "passive"))
      (node (ref "CN10") (pin "6") (pinfunction "Shield_6") (pintype "passive"))
      (node (ref "CN10") (pin "7") (pinfunction "Shield_7") (pintype "passive"))
      (node (ref "CN10") (pin "8") (pinfunction "Shield_8") (pintype "passive"))
      (node (ref "CN10") (pin "9") (pinfunction "Shield_9") (pintype "passive"))
      (node (ref "CN9") (pin "3") (pinfunction "3_3") (pintype "passive"))
      (node (ref "LD5") (pin "4") (pinfunction "RED_cathode_4") (pintype "passive"))
      (node (ref "R66") (pin "1") (pinfunction "1_1") (pintype "passive"))
      (node (ref "R68") (pin "2") (pinfunction "2_2") (pintype "passive"))
      (node (ref "R74") (pin "1") (pinfunction "1_1") (pintype "passive"))
      (node (ref "R84") (pin "1") (pinfunction "1_1") (pintype "passive"))
      (node (ref "R87") (pin "1") (pinfunction "1_1") (pintype "passive"))
      (node (ref "TP39") (pin "1") (pinfunction "1_1") (pintype "passive"))
      (node (ref "U11") (pin "2") (pinfunction "GND_2") (pintype "passive"))
      (node (ref "U12") (pin "D5") (pinfunction "VSS_D5") (pintype "passive"))
      (node (ref "U12") (pin "D6") (pinfunction "BOOT0_D6") (pintype "passive"))
      (node (ref "U12") (pin "D7") (pinfunction "VSS_D7") (pintype "passive"))
      (node (ref "U12") (pin "D8") (pinfunction "VSS_D8") (pintype "passive"))
      (node (ref "U12") (pin "D9") (pinfunction "VSS_D9") (pintype "passive"))
      (node (ref "U12") (pin "F10") (pinfunction "VSS_F10") (pintype "passive"))
      (node (ref "U12") (pin "F12") (pinfunction "VSS_F12") (pintype "passive"))
      (node (ref "U12") (pin "F2") (pinfunction "VSS_F2") (pintype "passive"))
      (node (ref "U12") (pin "F6") (pinfunction "VSS_F6") (pintype "passive"))
      (node (ref "U12") (pin "F7") (pinfunction "VSS_F7") (pintype "passive"))
      (node (ref "U12") (pin "F8") (pinfunction "VSS_F8") (pintype "passive"))
      (node (ref "U12") (pin "F9") (pinfunction "VSS_F9") (pintype "passive"))
      (node (ref "U12") (pin "G10") (pinfunction "VSS_G10") (pintype "passive"))
      (node (ref "U12") (pin "G12") (pinfunction "VSS_G12") (pintype "passive"))
      (node (ref "U12") (pin "G2") (pinfunction "VSS_G2") (pintype "passive"))
      (node (ref "U12") (pin "G6") (pinfunction "VSS_G6") (pintype "passive"))
      (node (ref "U12") (pin "G7") (pinfunction "VSS_G7") (pintype "passive"))
      (node (ref "U12") (pin "G8") (pinfunction "VSS_G8") (pintype "passive"))
      (node (ref "U12") (pin "G9") (pinfunction "VSS_G9") (pintype "passive"))
      (node (ref "U12") (pin "H10") (pinfunction "VSS_H10") (pintype "passive"))
      (node (ref "U12") (pin "H12") (pinfunction "VSS_H12") (pintype "passive"))
      (node (ref "U12") (pin "H6") (pinfunction "VSS_H6") (pintype "passive"))
      (node (ref "U12") (pin "H7") (pinfunction "VSS_H7") (pintype "passive"))
      (node (ref "U12") (pin "H8") (pinfunction "VSS_H8") (pintype "passive"))
      (node (ref "U12") (pin "H9") (pinfunction "VSS_H9") (pintype "passive"))
      (node (ref "U12") (pin "J10") (pinfunction "VSS_J10") (pintype "passive"))
      (node (ref "U12") (pin "J6") (pinfunction "VSS_J6") (pintype "passive"))
      (node (ref "U12") (pin "J7") (pinfunction "VSS_J7") (pintype "passive"))
      (node (ref "U12") (pin "J8") (pinfunction "VSS_J8") (pintype "passive"))
      (node (ref "U12") (pin "J9") (pinfunction "VSS_J9") (pintype "passive"))
      (node (ref "U12") (pin "K10") (pinfunction "VSS_K10") (pintype "passive"))
      (node (ref "U12") (pin "K6") (pinfunction "VSS_K6") (pintype "passive"))
      (node (ref "U12") (pin "K7") (pinfunction "VSS_K7") (pintype "passive"))
      (node (ref "U12") (pin "K8") (pinfunction "VSS_K8") (pintype "passive"))
      (node (ref "U12") (pin "K9") (pinfunction "VSS_K9") (pintype "passive"))
      (node (ref "U12") (pin "M1") (pinfunction "VSSA_M1") (pintype "passive"))
      (node (ref "U12") (pin "M8") (pinfunction "VSS_M8") (pintype "passive"))
      (node (ref "U12") (pin "M9") (pinfunction "VSS_M9") (pintype "passive"))
      (node (ref "U12") (pin "N1") (pinfunction "VREF-_N1") (pintype "passive"))
      (node (ref "U16") (pin "2") (pinfunction "GND_2") (pintype "passive"))
      (node (ref "U18") (pin "3") (pinfunction "GND_3") (pintype "passive"))
      (node (ref "X1") (pin "2") (pinfunction "GND_2") (pintype "passive"))
    )
    (net (code "29") (name "Net-(D1-K)") (class "Default")
      (node (ref "D1") (pin "2") (pinfunction "K_2") (pintype "passive"))
      (node (ref "D3") (pin "2") (pinfunction "K_2") (pintype "passive"))
      (node (ref "R45") (pin "1") (pinfunction "1_1") (pintype "passive"))
    )
    (net (code "30") (name "Net-(LD5-Red_anode)") (class "Default")
      (node (ref "LD5") (pin "2") (pinfunction "Red_anode_2") (pintype "passive"))
      (node (ref "R117") (pin "1") (pinfunction "1_1") (pintype "passive"))
    )
    (net (code "31") (name "Net-(LD5-YellowGreen_cathode)") (class "Default")
      (node (ref "LD5") (pin "1") (pinfunction "YellowGreen_cathode_1") (pintype "passive"))
      (node (ref "R125") (pin "1") (pinfunction "1_1") (pintype "passive"))
    )
    (net (code "32") (name "Net-(U11-BYPASS)") (class "Default")
      (node (ref "C55") (pin "2") (pinfunction "2_2") (pintype "passive"))
      (node (ref "U11") (pin "4") (pinfunction "BYPASS_4") (pintype "passive"))
    )
    (net (code "33") (name "Net-(U11-CE)") (class "Default")
      (node (ref "C36") (pin "1") (pinfunction "1_1") (pintype "passive"))
      (node (ref "C41") (pin "2") (pinfunction "2_2") (pintype "passive"))
      (node (ref "R45") (pin "2") (pinfunction "2_2") (pintype "passive"))
      (node (ref "U11") (pin "1") (pinfunction "Vin_1") (pintype "passive"))
      (node (ref "U11") (pin "3") (pinfunction "CE_3") (pintype "passive"))
    )
    (net (code "34") (name "Net-(U12A-OSC_IN{slash}PH0)") (class "Default")
      (node (ref "U12") (pin "G1") (pinfunction "OSC_IN/PH0_G1") (pintype "passive"))
      (node (ref "X1") (pin "3") (pinfunction "OUT_3") (pintype "passive"))
    )
    (net (code "35") (name "Net-(U12A-REXT_OTGPHY)") (class "Default")
      (node (ref "R66") (pin "2") (pinfunction "2_2") (pintype "passive"))
      (node (ref "U12") (pin "J15") (pinfunction "REXT_OTGPHY_J15") (pintype "passive"))
    )
    (net (code "36") (name "Net-(U12A-STLK_VCP_RX{slash}PG9)") (class "Default")
      (node (ref "R55") (pin "1") (pinfunction "1_1") (pintype "passive"))
      (node (ref "U12") (pin "C10") (pinfunction "STLK_VCP_RX/PG9_C10") (pintype "passive"))
    )
    (net (code "37") (name "Net-(U12A-STLK_VCP_TX{slash}PG14)") (class "Default")
      (node (ref "R54") (pin "1") (pinfunction "1_1") (pintype "passive"))
      (node (ref "U12") (pin "A7") (pinfunction "STLK_VCP_TX/PG14_A7") (pintype "passive"))
    )
    (net (code "38") (name "Net-(U12A-T_VCC_AIN{slash}PA0)") (class "Default")
      (node (ref "R87") (pin "2") (pinfunction "2_2") (pintype "passive"))
      (node (ref "R94") (pin "1") (pinfunction "1_1") (pintype "passive"))
      (node (ref "U12") (pin "N3") (pinfunction "T_VCC_AIN/PA0_N3") (pintype "passive"))
    )
    (net (code "39") (name "Net-(U12A-V12_OTGPHY)") (class "Default")
      (node (ref "C64") (pin "2") (pinfunction "2_2") (pintype "passive"))
      (node (ref "U12") (pin "J14") (pinfunction "V12_OTGPHY_J14") (pintype "passive"))
    )
    (net (code "40") (name "Net-(U12B-UART_RX{slash}PB11)") (class "Default")
      (node (ref "R91") (pin "2") (pinfunction "2_2") (pintype "passive"))
      (node (ref "TP48") (pin "1") (pinfunction "1_1") (pintype "passive"))
      (node (ref "U12") (pin "R13") (pinfunction "UART_RX/PB11_R13") (pintype "passive"))
    )
    (net (code "41") (name "Net-(U12B-UART_TX{slash}PC10)") (class "Default")
      (node (ref "R56") (pin "2") (pinfunction "2_2") (pintype "passive"))
      (node (ref "TP38") (pin "1") (pinfunction "1_1") (pintype "passive"))
      (node (ref "U12") (pin "B14") (pinfunction "UART_TX/PC10_B14") (pintype "passive"))
    )
    (net (code "42") (name "Net-(U12C-BYPASS-REG)") (class "Default")
      (node (ref "R84") (pin "2") (pinfunction "2_2") (pintype "passive"))
      (node (ref "U12") (pin "L4") (pinfunction "BYPASS-REG_L4") (pintype "passive"))
    )
    (net (code "43") (name "Net-(U12C-VCAP1)") (class "Default")
      (node (ref "C73") (pin "2") (pinfunction "2_2") (pintype "passive"))
      (node (ref "U12") (pin "M10") (pinfunction "VCAP1_M10") (pintype "passive"))
    )
    (net (code "44") (name "Net-(U12C-VCAP2)") (class "Default")
      (node (ref "C60") (pin "2") (pinfunction "2_2") (pintype "passive"))
      (node (ref "U12") (pin "F13") (pinfunction "VCAP2_F13") (pintype "passive"))
    )
    (net (code "45") (name "Net-(X1-EN)") (class "Default")
      (node (ref "R65") (pin "2") (pinfunction "2_2") (pintype "passive"))
      (node (ref "X1") (pin "1") (pinfunction "EN_1") (pintype "passive"))
    )
    (net (code "46") (name "VDD") (class "Default")
      (node (ref "R94") (pin "2") (pinfunction "2_2") (pintype "passive"))
    )
    (net (code "47") (name "unconnected-(CN10-ID-Pad4)") (class "Default")
      (node (ref "CN10") (pin "4") (pinfunction "ID_4") (pintype "passive+no_connect"))
    )
    (net (code "48") (name "unconnected-(U12A-HW_TYP_0{slash}PI4-PadD4)") (class "Default")
      (node (ref "U12") (pin "D4") (pinfunction "HW_TYP_0/PI4_D4") (pintype "passive+no_connect"))
    )
    (net (code "49") (name "unconnected-(U12A-HW_TYP_1{slash}PI5-PadC4)") (class "Default")
      (node (ref "U12") (pin "C4") (pinfunction "HW_TYP_1/PI5_C4") (pintype "passive+no_connect"))
    )
    (net (code "50") (name "unconnected-(U12A-SWIM_IN_ack{slash}PC7-PadG15)") (class "Default")
      (node (ref "U12") (pin "G15") (pinfunction "SWIM_IN_ack/PC7_G15") (pintype "passive+no_connect"))
    )
    (net (code "51") (name "unconnected-(U12A-SWIM_IN_data{slash}PC8-PadG14)") (class "Default")
      (node (ref "U12") (pin "G14") (pinfunction "SWIM_IN_data/PC8_G14") (pintype "passive+no_connect"))
    )
    (net (code "52") (name "unconnected-(U12A-SWIM_OUT{slash}PA1-PadN2)") (class "Default")
      (node (ref "U12") (pin "N2") (pinfunction "SWIM_OUT/PA1_N2") (pintype "passive+no_connect"))
    )
    (net (code "53") (name "unconnected-(U12A-T_JNRST{slash}PF13-PadN6)") (class "Default")
      (node (ref "U12") (pin "N6") (pinfunction "T_JNRST/PF13_N6") (pintype "passive+no_connect"))
    )
    (net (code "54") (name "unconnected-(U12A-T_SW_DIR{slash}PA7-PadR3)") (class "Default")
      (node (ref "U12") (pin "R3") (pinfunction "T_SW_DIR/PA7_R3") (pintype "passive+no_connect"))
    )
    (net (code "55") (name "unconnected-(U12B-CAN_RX{slash}PA11-PadC15)") (class "Default")
      (node (ref "U12") (pin "C15") (pinfunction "CAN_RX/PA11_C15") (pintype "passive+no_connect"))
    )
    (net (code "56") (name "unconnected-(U12B-CAN_TX{slash}PA12-PadB15)") (class "Default")
      (node (ref "U12") (pin "B15") (pinfunction "CAN_TX/PA12_B15") (pintype "passive+no_connect"))
    )
    (net (code "57") (name "unconnected-(U12B-GPIO0{slash}PE2-PadA2)") (class "Default")
      (node (ref "U12") (pin "A2") (pinfunction "GPIO0/PE2_A2") (pintype "passive+no_connect"))
    )
    (net (code "58") (name "unconnected-(U12B-GPIO1{slash}PE4-PadB1)") (class "Default")
      (node (ref "U12") (pin "B1") (pinfunction "GPIO1/PE4_B1") (pintype "passive+no_connect"))
    )
    (net (code "59") (name "unconnected-(U12B-GPIO2{slash}PE5-PadB2)") (class "Default")
      (node (ref "U12") (pin "B2") (pinfunction "GPIO2/PE5_B2") (pintype "passive+no_connect"))
    )
    (net (code "60") (name "unconnected-(U12B-GPIO3{slash}PE6-PadB3)") (class "Default")
      (node (ref "U12") (pin "B3") (pinfunction "GPIO3/PE6_B3") (pintype "passive+no_connect"))
    )
    (net (code "61") (name "unconnected-(U12B-I2C_SCL{slash}PB8-PadA5)") (class "Default")
      (node (ref "U12") (pin "A5") (pinfunction "I2C_SCL/PB8_A5") (pintype "passive+no_connect"))
    )
    (net (code "62") (name "unconnected-(U12B-I2C_SDA{slash}PB9-PadB4)") (class "Default")
      (node (ref "U12") (pin "B4") (pinfunction "I2C_SDA/PB9_B4") (pintype "passive+no_connect"))
    )
    (net (code "63") (name "unconnected-(U12B-SPI_MISO{slash}PC2-PadM4)") (class "Default")
      (node (ref "U12") (pin "M4") (pinfunction "SPI_MISO/PC2_M4") (pintype "passive+no_connect"))
    )
    (net (code "64") (name "unconnected-(U12B-SPI_MOSI{slash}PC1-PadM3)") (class "Default")
      (node (ref "U12") (pin "M3") (pinfunction "SPI_MOSI/PC1_M3") (pintype "passive+no_connect"))
    )
    (net (code "65") (name "unconnected-(U12B-SPI_NSS{slash}PB4-PadA9)") (class "Default")
      (node (ref "U12") (pin "A9") (pinfunction "SPI_NSS/PB4_A9") (pintype "passive+no_connect"))
    )
    (net (code "66") (name "unconnected-(U12B-SPI_SCK{slash}PA9-PadE15)") (class "Default")
      (node (ref "U12") (pin "E15") (pinfunction "SPI_SCK/PA9_E15") (pintype "passive+no_connect"))
    )
    (net (code "67") (name "unconnected-(U12B-UART_CTS{slash}PD11-PadN14)") (class "Default")
      (node (ref "U12") (pin "N14") (pinfunction "UART_CTS/PD11_N14") (pintype "passive+no_connect"))
    )
    (net (code "68") (name "unconnected-(U12B-UART_RTS{slash}PD12-PadN13)") (class "Default")
      (node (ref "U12") (pin "N13") (pinfunction "UART_RTS/PD12_N13") (pintype "passive+no_connect"))
    )
    (net (code "69") (name "unconnected-(U18-NC-Pad4)") (class "Default")
      (node (ref "U18") (pin "4") (pinfunction "NC_4") (pintype "passive+no_connect"))
    )
  )
)
